# RCMx1_Rev_03.net
KiCad netlist of a schematic drawn in EAGLE
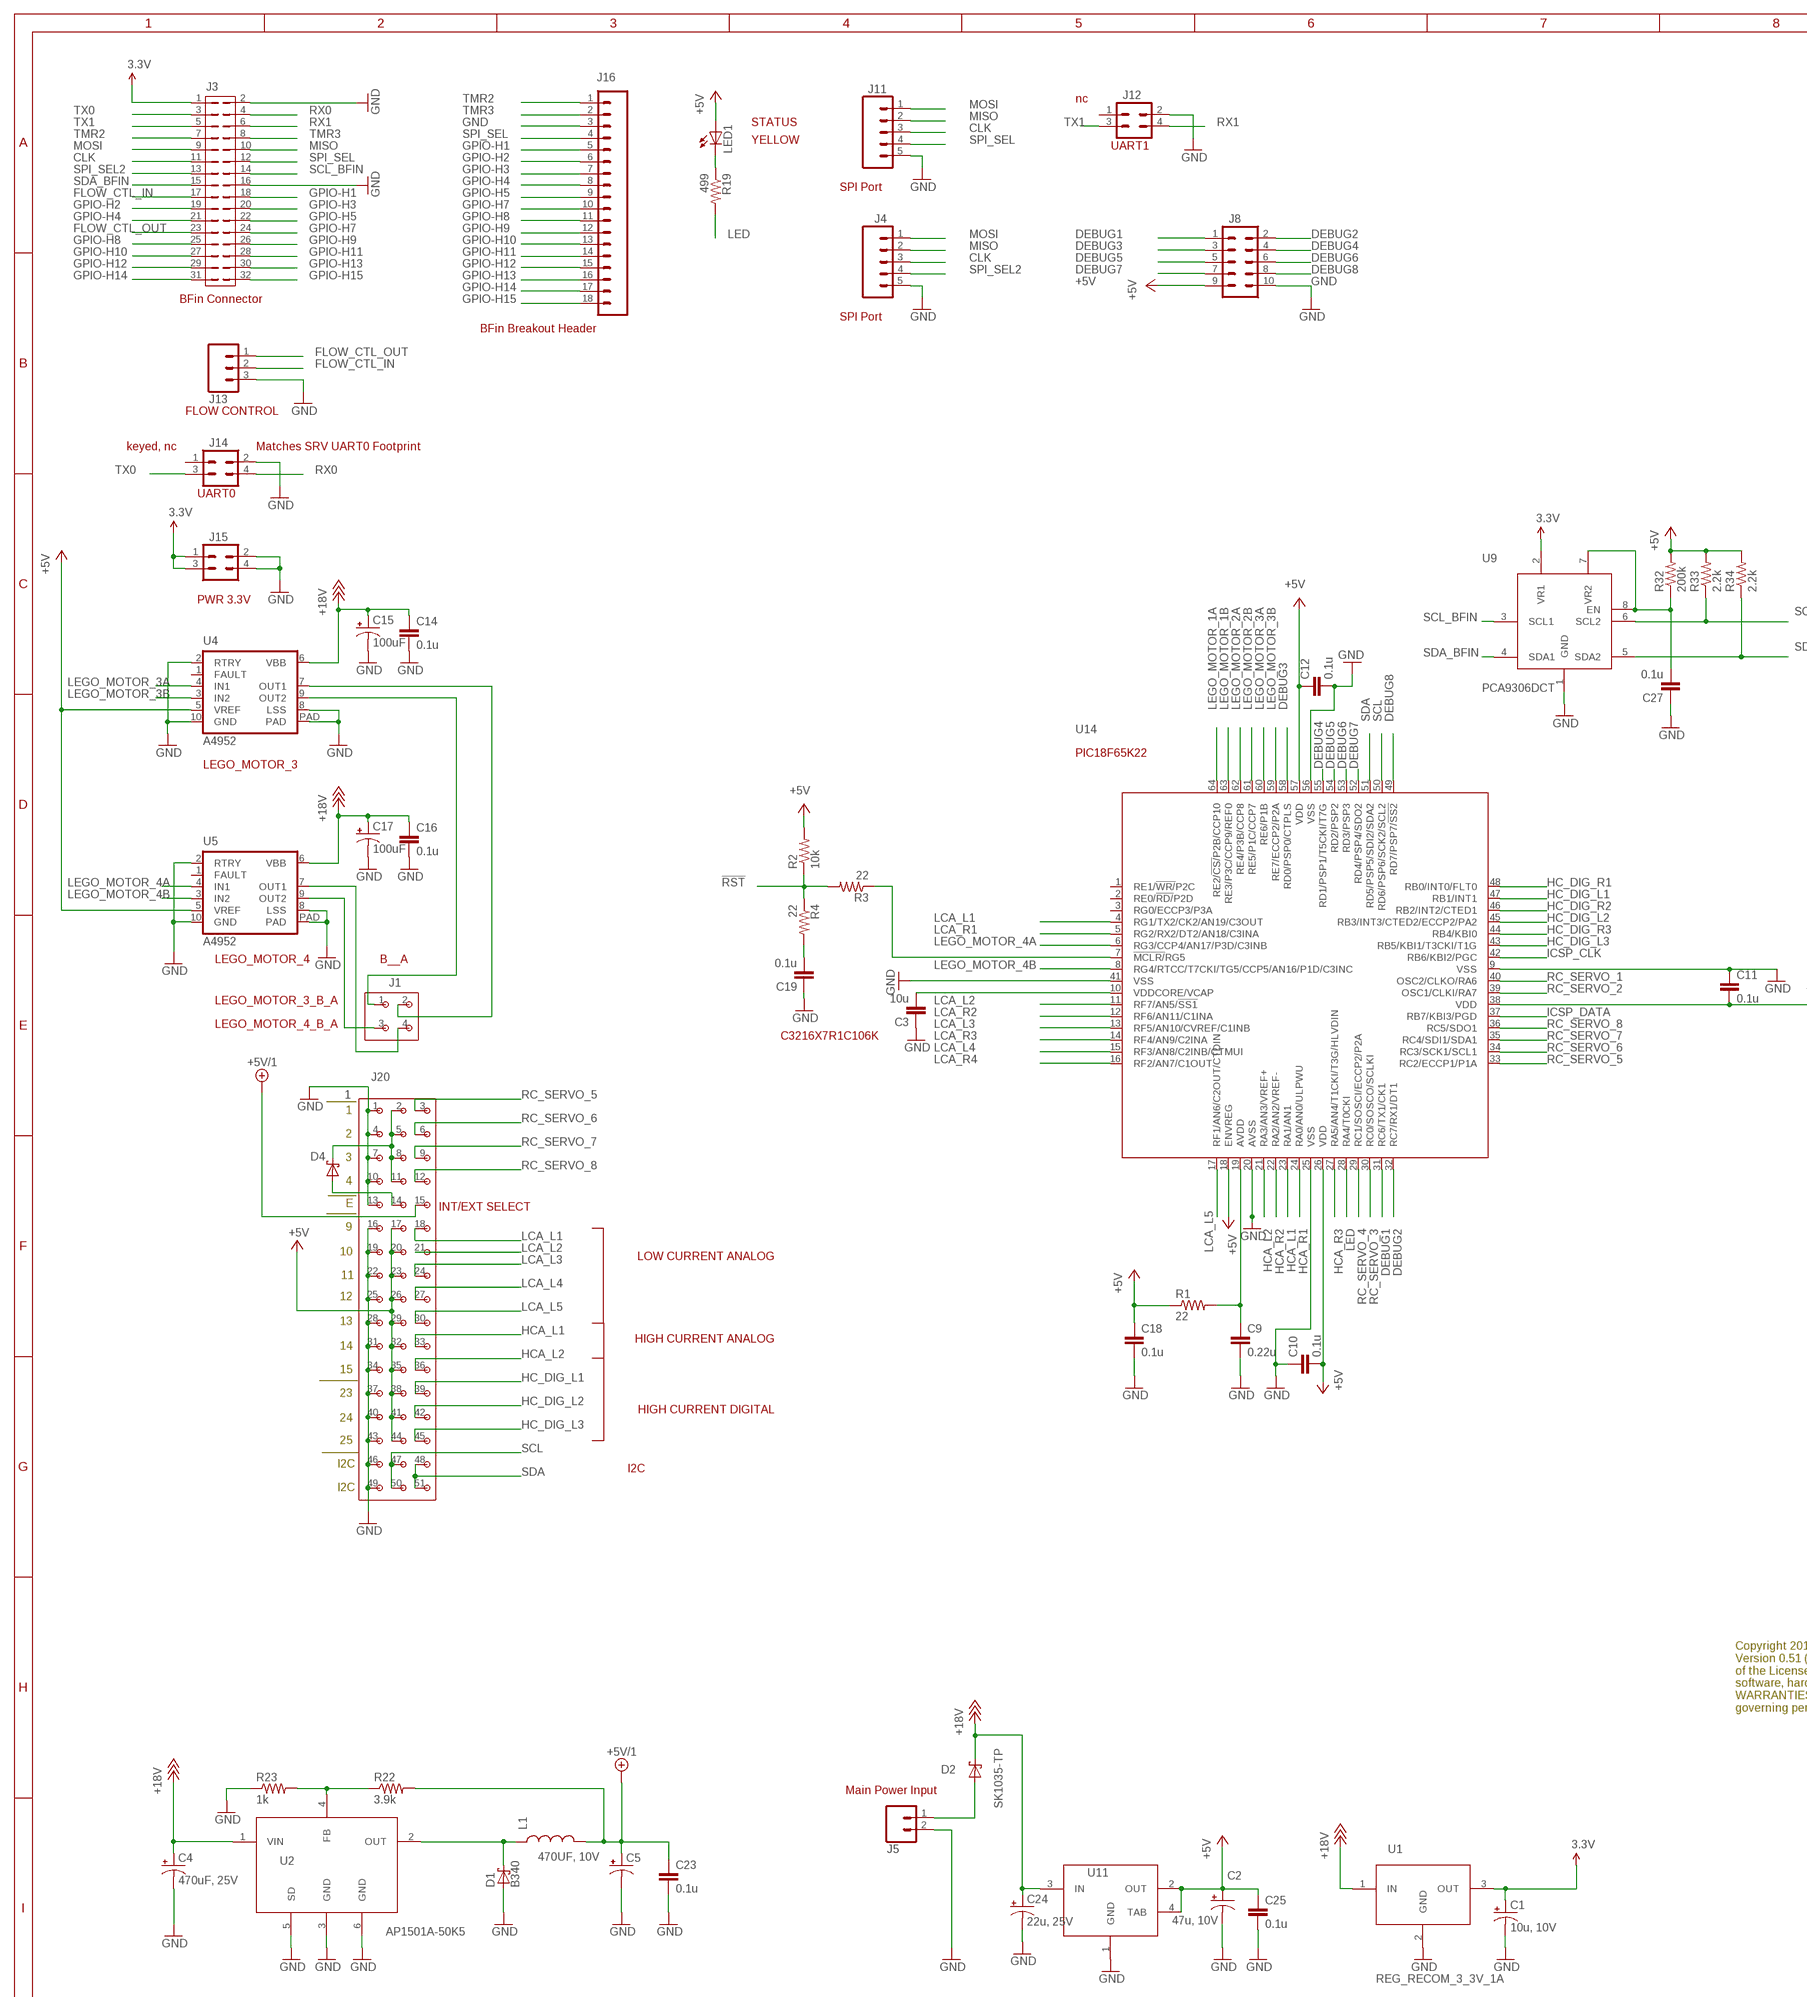
[diagram p0: schematic, sheet 1, part 1 of 2]
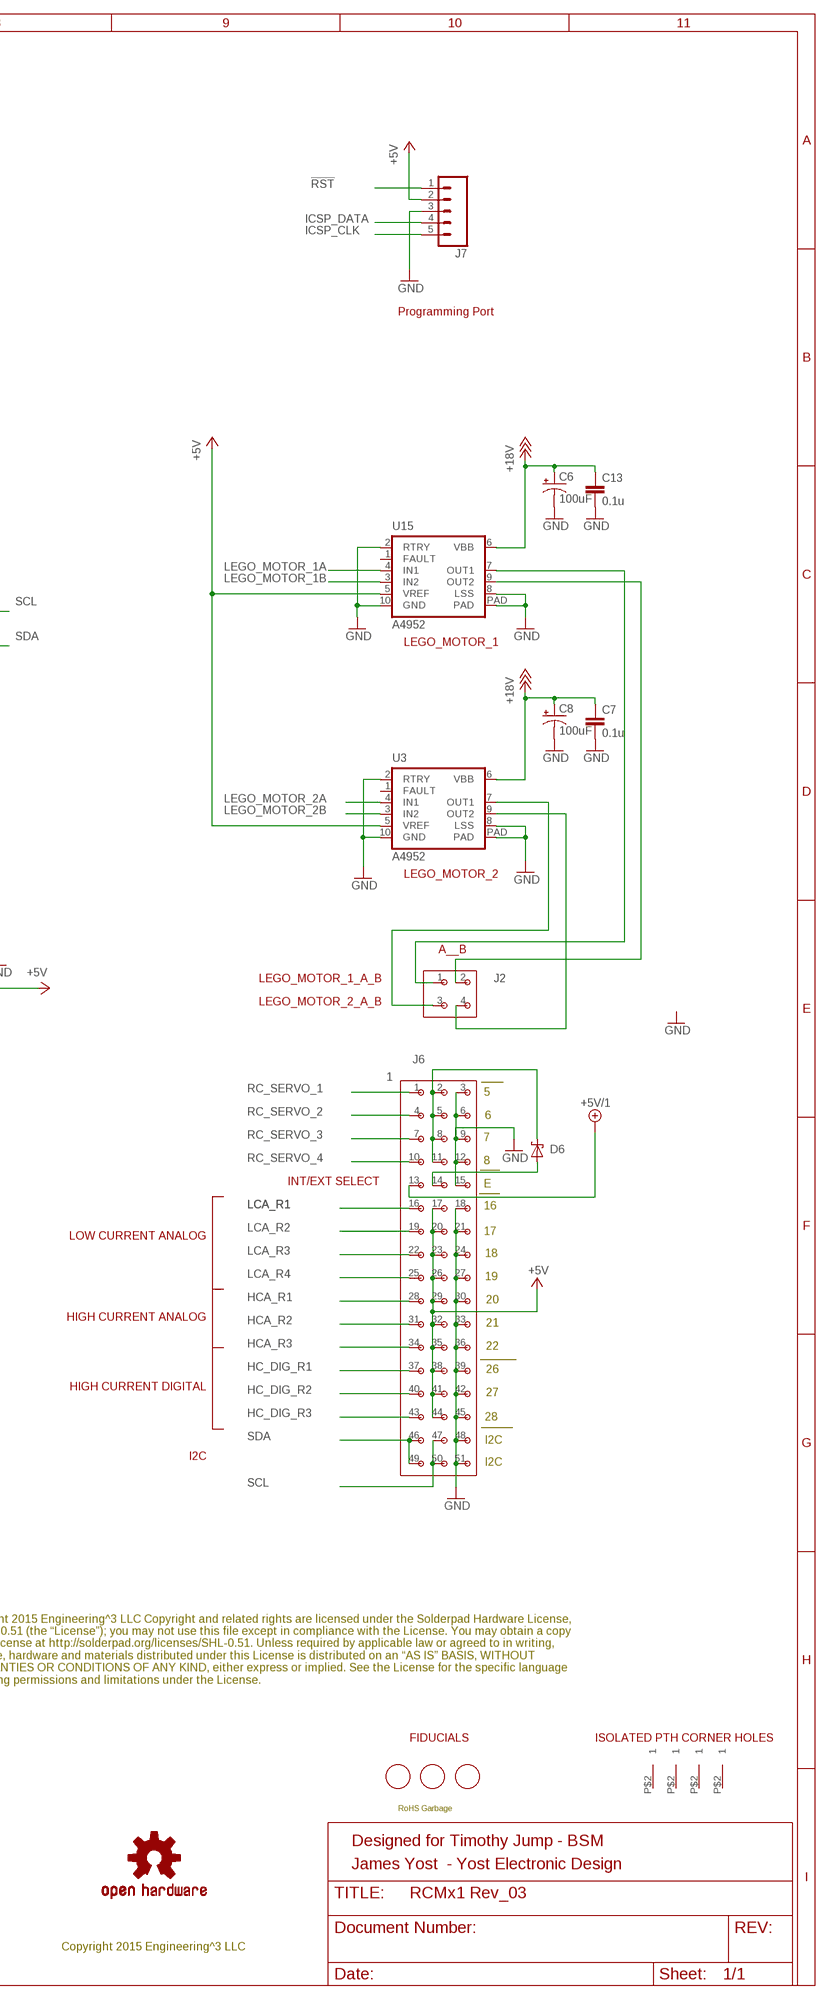
[diagram p1: schematic, sheet 1, part 2 of 2]

(export (version "E")
  (design (tool "Eeschema 10.0.6"))
  (components
    (comp (ref "C1")
      (value "10u, 10V")
      (footprint "eagle-import:EIA3216")
      (libsource (lib "eagle-import") (part "CAP_POL1206"))
    )
    (comp (ref "C2")
      (value "47u, 10V")
      (footprint "eagle-import:CAP1210_POL")
      (libsource (lib "eagle-import") (part "CAP_1210_POL"))
    )
    (comp (ref "C3")
      (value "10u")
      (footprint "eagle-import:1206")
      (libsource (lib "eagle-import") (part "CAP1206"))
    )
    (comp (ref "C4")
      (value "470uF, 25V")
      (footprint "eagle-import:PANASONIC_G")
      (libsource (lib "eagle-import") (part "CAP_POLG"))
    )
    (comp (ref "C5")
      (value "470UF, 10V")
      (footprint "eagle-import:PANASONIC_F")
      (libsource (lib "eagle-import") (part "CAP_ELT_PANASONIC_470UF"))
    )
    (comp (ref "C6")
      (value "100uF")
      (footprint "eagle-import:PANASONIC_D")
      (libsource (lib "eagle-import") (part "CAP_POLD"))
    )
    (comp (ref "C7")
      (value "0.1u")
      (footprint "eagle-import:0805")
      (libsource (lib "eagle-import") (part "CAP0805"))
    )
    (comp (ref "C8")
      (value "100uF")
      (footprint "eagle-import:PANASONIC_D")
      (libsource (lib "eagle-import") (part "CAP_POLD"))
    )
    (comp (ref "C9")
      (value "0.22u")
      (footprint "eagle-import:0805")
      (libsource (lib "eagle-import") (part "CAP0805"))
    )
    (comp (ref "C10")
      (value "0.1u")
      (footprint "eagle-import:0805")
      (libsource (lib "eagle-import") (part "CAP0805"))
    )
    (comp (ref "C11")
      (value "0.1u")
      (footprint "eagle-import:0805")
      (libsource (lib "eagle-import") (part "CAP0805"))
    )
    (comp (ref "C12")
      (value "0.1u")
      (footprint "eagle-import:0805")
      (libsource (lib "eagle-import") (part "CAP0805"))
    )
    (comp (ref "C13")
      (value "0.1u")
      (footprint "eagle-import:0805")
      (libsource (lib "eagle-import") (part "CAP0805"))
    )
    (comp (ref "C14")
      (value "0.1u")
      (footprint "eagle-import:0805")
      (libsource (lib "eagle-import") (part "CAP0805"))
    )
    (comp (ref "C15")
      (value "100uF")
      (footprint "eagle-import:PANASONIC_D")
      (libsource (lib "eagle-import") (part "CAP_POLD"))
    )
    (comp (ref "C16")
      (value "0.1u")
      (footprint "eagle-import:0805")
      (libsource (lib "eagle-import") (part "CAP0805"))
    )
    (comp (ref "C17")
      (value "100uF")
      (footprint "eagle-import:PANASONIC_D")
      (libsource (lib "eagle-import") (part "CAP_POLD"))
    )
    (comp (ref "C18")
      (value "0.1u")
      (footprint "eagle-import:0805")
      (libsource (lib "eagle-import") (part "CAP0805"))
    )
    (comp (ref "C19")
      (value "0.1u")
      (footprint "eagle-import:0805")
      (libsource (lib "eagle-import") (part "CAP0805"))
    )
    (comp (ref "C23")
      (value "0.1u")
      (footprint "eagle-import:0805")
      (libsource (lib "eagle-import") (part "CAP0805"))
    )
    (comp (ref "C24")
      (value "22u, 25V")
      (footprint "eagle-import:CAP1210_POL")
      (libsource (lib "eagle-import") (part "CAP_1210_POL"))
    )
    (comp (ref "C25")
      (value "0.1u")
      (footprint "eagle-import:0805")
      (libsource (lib "eagle-import") (part "CAP0805"))
    )
    (comp (ref "C27")
      (value "0.1u")
      (footprint "eagle-import:0805")
      (libsource (lib "eagle-import") (part "CAP0805"))
    )
    (comp (ref "D1")
      (value "B340")
      (footprint "eagle-import:SMA_DO214AC")
      (libsource (lib "eagle-import") (part "B340"))
    )
    (comp (ref "D2")
      (value "SK1035-TP")
      (footprint "eagle-import:DO214AB")
      (libsource (lib "eagle-import") (part "SK1035-TP"))
    )
    (comp (ref "D4")
      (value "SK1035-TP")
      (footprint "eagle-import:DO214AB")
      (libsource (lib "eagle-import") (part "SK1035-TP"))
    )
    (comp (ref "D6")
      (value "SK1035-TP")
      (footprint "eagle-import:DO214AB")
      (libsource (lib "eagle-import") (part "SK1035-TP"))
    )
    (comp (ref "FID1")
      (value "FIDUCIAL")
      (footprint "eagle-import:FIDUCIAL_1MM")
      (libsource (lib "eagle-import") (part "FIDUCIAL"))
    )
    (comp (ref "FID2")
      (value "FIDUCIAL")
      (footprint "eagle-import:FIDUCIAL_1MM")
      (libsource (lib "eagle-import") (part "FIDUCIAL"))
    )
    (comp (ref "FID3")
      (value "FIDUCIAL")
      (footprint "eagle-import:FIDUCIAL_1MM")
      (libsource (lib "eagle-import") (part "FIDUCIAL"))
    )
    (comp (ref "J1")
      (value "CON_2X2_0_100")
      (footprint "eagle-import:CON_2X2_0_100")
      (libsource (lib "eagle-import") (part "CON_2X2_0_100"))
    )
    (comp (ref "J2")
      (value "CON_2X2_0_100")
      (footprint "eagle-import:CON_2X2_0_100")
      (libsource (lib "eagle-import") (part "CON_2X2_0_100"))
    )
    (comp (ref "J3")
      (value "CON_2X16_0_100")
      (footprint "eagle-import:CON_2X16_0_100")
      (libsource (lib "eagle-import") (part "CON_2X16_0_100"))
    )
    (comp (ref "J4")
      (value "M05PTH")
      (footprint "eagle-import:1X05")
      (libsource (lib "eagle-import") (part "M05PTH"))
    )
    (comp (ref "J5")
      (value "M02NG")
      (footprint "eagle-import:1X02")
      (libsource (lib "eagle-import") (part "M02NG"))
    )
    (comp (ref "J6")
      (value "CON_3X17_0_100")
      (footprint "eagle-import:CON_3X17_0_100")
      (libsource (lib "eagle-import") (part "CON_3X17_0_100"))
    )
    (comp (ref "J7")
      (value "M05PTH")
      (footprint "eagle-import:1X05")
      (libsource (lib "eagle-import") (part "SparkFun-Connectors_M05PTH"))
    )
    (comp (ref "J8")
      (value "M05X2PTH")
      (footprint "eagle-import:AVR_ICSP")
      (libsource (lib "eagle-import") (part "M05X2PTH"))
    )
    (comp (ref "J11")
      (value "M05PTH")
      (footprint "eagle-import:1X05")
      (libsource (lib "eagle-import") (part "M05PTH"))
    )
    (comp (ref "J12")
      (value "CON2X2")
      (footprint "eagle-import:CON2X2")
      (libsource (lib "eagle-import") (part "CON2X2"))
    )
    (comp (ref "J13")
      (value "M03PTH")
      (footprint "eagle-import:1X03")
      (libsource (lib "eagle-import") (part "M03PTH"))
    )
    (comp (ref "J14")
      (value "CON2X2")
      (footprint "eagle-import:CON2X2")
      (libsource (lib "eagle-import") (part "CON2X2"))
    )
    (comp (ref "J15")
      (value "CON2X2")
      (footprint "eagle-import:CON2X2")
      (libsource (lib "eagle-import") (part "CON2X2"))
    )
    (comp (ref "J16")
      (value "CON1X18")
      (footprint "eagle-import:CON1X18")
      (libsource (lib "eagle-import") (part "CON1X18"))
    )
    (comp (ref "J20")
      (value "CON_3X17_0_100")
      (footprint "eagle-import:CON_3X17_0_100")
      (libsource (lib "eagle-import") (part "CON_3X17_0_100"))
    )
    (comp (ref "L1")
      (value "IND_47UH_COILTRONICS_2_95A")
      (footprint "eagle-import:IND_PADS_SMT")
      (libsource (lib "eagle-import") (part "IND_47UH_COILTRONICS_2_95A"))
    )
    (comp (ref "LED1")
      (value "LEDCHIP-LED0805")
      (footprint "eagle-import:CHIP-LED0805")
      (libsource (lib "eagle-import") (part "LEDCHIP-LED0805"))
    )
    (comp (ref "LOGO1")
      (value "OSHW-LOGOM")
      (footprint "eagle-import:OSHW-LOGO-M")
      (libsource (lib "eagle-import") (part "OSHW-LOGOM"))
    )
    (comp (ref "R1")
      (value "22")
      (footprint "eagle-import:0805")
      (libsource (lib "eagle-import") (part "RESISTOR"))
    )
    (comp (ref "R2")
      (value "10k")
      (footprint "eagle-import:0805")
      (libsource (lib "eagle-import") (part "RESISTOR"))
    )
    (comp (ref "R3")
      (value "22")
      (footprint "eagle-import:0805")
      (libsource (lib "eagle-import") (part "RESISTOR"))
    )
    (comp (ref "R4")
      (value "22")
      (footprint "eagle-import:0805")
      (libsource (lib "eagle-import") (part "RESISTOR"))
    )
    (comp (ref "R19")
      (value "499")
      (footprint "eagle-import:0805")
      (libsource (lib "eagle-import") (part "RESISTOR"))
    )
    (comp (ref "R22")
      (value "3.9k")
      (footprint "eagle-import:0805")
      (libsource (lib "eagle-import") (part "RESISTOR"))
    )
    (comp (ref "R23")
      (value "1k")
      (footprint "eagle-import:0805")
      (libsource (lib "eagle-import") (part "RESISTOR"))
    )
    (comp (ref "R32")
      (value "200k")
      (footprint "eagle-import:0805")
      (libsource (lib "eagle-import") (part "RESISTOR"))
    )
    (comp (ref "R33")
      (value "2.2k")
      (footprint "eagle-import:0805")
      (libsource (lib "eagle-import") (part "RESISTOR"))
    )
    (comp (ref "R34")
      (value "2.2k")
      (footprint "eagle-import:0805")
      (libsource (lib "eagle-import") (part "RESISTOR"))
    )
    (comp (ref "U$1")
      (value "GNDPAD")
      (footprint "eagle-import:GNDPAD")
      (libsource (lib "eagle-import") (part "GNDPAD"))
    )
    (comp (ref "U$2")
      (value "GNDPAD")
      (footprint "eagle-import:GNDPAD")
      (libsource (lib "eagle-import") (part "GNDPAD"))
    )
    (comp (ref "U$3")
      (value "ROHS_GARBAGE")
      (footprint "eagle-import:ROHS_GARBAGE_5MM")
      (libsource (lib "eagle-import") (part "ROHS_GARBAGE"))
    )
    (comp (ref "U$7")
      (value "GNDPAD")
      (footprint "eagle-import:GNDPAD")
      (libsource (lib "eagle-import") (part "GNDPAD"))
    )
    (comp (ref "U$8")
      (value "GNDPAD")
      (footprint "eagle-import:GNDPAD")
      (libsource (lib "eagle-import") (part "GNDPAD"))
    )
    (comp (ref "U1")
      (value "REG_RECOM_3_3V_1A")
      (footprint "eagle-import:REG_RECOM_3_3V_1A")
      (libsource (lib "eagle-import") (part "REG_RECOM_3_3V_1A"))
    )
    (comp (ref "U2")
      (value "AP1501A-50K5")
      (footprint "eagle-import:TO263-5")
      (libsource (lib "eagle-import") (part "AP1501A-50K5"))
    )
    (comp (ref "U3")
      (value "A4952")
      (footprint "eagle-import:MSOP10_W_THERMAL_PAD")
      (libsource (lib "eagle-import") (part "A4952"))
    )
    (comp (ref "U4")
      (value "A4952")
      (footprint "eagle-import:MSOP10_W_THERMAL_PAD")
      (libsource (lib "eagle-import") (part "A4952"))
    )
    (comp (ref "U5")
      (value "A4952")
      (footprint "eagle-import:MSOP10_W_THERMAL_PAD")
      (libsource (lib "eagle-import") (part "A4952"))
    )
    (comp (ref "U9")
      (value "PCA9306DCT")
      (footprint "eagle-import:TEST08")
      (libsource (lib "eagle-import") (part "PCA9306DCT"))
    )
    (comp (ref "U11")
      (value "TLV1117-5")
      (footprint "eagle-import:SOT223")
      (libsource (lib "eagle-import") (part "TLV1117-5"))
    )
    (comp (ref "U14")
      (value "MICRO_C_PIC18F65K22")
      (footprint "eagle-import:64PIN_TQFP_10X10X1MM")
      (libsource (lib "eagle-import") (part "MICRO_C_PIC18F65K22"))
    )
    (comp (ref "U15")
      (value "A4952")
      (footprint "eagle-import:MSOP10_W_THERMAL_PAD")
      (libsource (lib "eagle-import") (part "A4952"))
    )
  )
  (nets
    (net (code "1") (name "+5V") (class "Default")
      (node (ref "C10") (pin "2") (pinfunction "2_2") (pintype "passive"))
      (node (ref "C11") (pin "2") (pinfunction "2_2") (pintype "passive"))
      (node (ref "C12") (pin "1") (pinfunction "1_1") (pintype "passive"))
      (node (ref "C18") (pin "1") (pinfunction "1_1") (pintype "passive"))
      (node (ref "C2") (pin "1") (pinfunction "+_1") (pintype "passive"))
      (node (ref "C25") (pin "1") (pinfunction "1_1") (pintype "passive"))
      (node (ref "J20") (pin "17") (pinfunction "17_17") (pintype "passive"))
      (node (ref "J20") (pin "20") (pinfunction "20_20") (pintype "passive"))
      (node (ref "J20") (pin "23") (pinfunction "23_23") (pintype "passive"))
      (node (ref "J20") (pin "26") (pinfunction "26_26") (pintype "passive"))
      (node (ref "J20") (pin "29") (pinfunction "29_29") (pintype "passive"))
      (node (ref "J20") (pin "32") (pinfunction "32_32") (pintype "passive"))
      (node (ref "J20") (pin "35") (pinfunction "35_35") (pintype "passive"))
      (node (ref "J20") (pin "38") (pinfunction "38_38") (pintype "passive"))
      (node (ref "J20") (pin "41") (pinfunction "41_41") (pintype "passive"))
      (node (ref "J20") (pin "44") (pinfunction "44_44") (pintype "passive"))
      (node (ref "J6") (pin "17") (pinfunction "17_17") (pintype "passive"))
      (node (ref "J6") (pin "20") (pinfunction "20_20") (pintype "passive"))
      (node (ref "J6") (pin "23") (pinfunction "23_23") (pintype "passive"))
      (node (ref "J6") (pin "26") (pinfunction "26_26") (pintype "passive"))
      (node (ref "J6") (pin "29") (pinfunction "29_29") (pintype "passive"))
      (node (ref "J6") (pin "32") (pinfunction "32_32") (pintype "passive"))
      (node (ref "J6") (pin "35") (pinfunction "35_35") (pintype "passive"))
      (node (ref "J6") (pin "38") (pinfunction "38_38") (pintype "passive"))
      (node (ref "J6") (pin "41") (pinfunction "41_41") (pintype "passive"))
      (node (ref "J6") (pin "44") (pinfunction "44_44") (pintype "passive"))
      (node (ref "J7") (pin "2") (pinfunction "2_2") (pintype "passive"))
      (node (ref "J8") (pin "9") (pinfunction "9_9") (pintype "passive"))
      (node (ref "LED1") (pin "A") (pinfunction "A_A") (pintype "passive"))
      (node (ref "R1") (pin "1") (pinfunction "1_1") (pintype "passive"))
      (node (ref "R2") (pin "2") (pinfunction "2_2") (pintype "passive"))
      (node (ref "R32") (pin "2") (pinfunction "2_2") (pintype "passive"))
      (node (ref "R33") (pin "2") (pinfunction "2_2") (pintype "passive"))
      (node (ref "R34") (pin "2") (pinfunction "2_2") (pintype "passive"))
      (node (ref "U11") (pin "2") (pinfunction "OUT_2") (pintype "bidirectional"))
      (node (ref "U11") (pin "4") (pinfunction "TAB_4") (pintype "bidirectional"))
      (node (ref "U14") (pin "18") (pinfunction "ENVREG_18") (pintype "input"))
      (node (ref "U14") (pin "26") (pinfunction "VDD_26") (pintype "power_in"))
      (node (ref "U14") (pin "38") (pinfunction "VDD_38") (pintype "power_in"))
      (node (ref "U14") (pin "57") (pinfunction "VDD_57") (pintype "power_in"))
      (node (ref "U15") (pin "5") (pinfunction "VREF_5") (pintype "passive"))
      (node (ref "U3") (pin "5") (pinfunction "VREF_5") (pintype "passive"))
      (node (ref "U4") (pin "5") (pinfunction "VREF_5") (pintype "passive"))
      (node (ref "U5") (pin "5") (pinfunction "VREF_5") (pintype "passive"))
    )
    (net (code "2") (name "+5V{slash}1") (class "Default")
      (node (ref "C23") (pin "1") (pinfunction "1_1") (pintype "passive"))
      (node (ref "C5") (pin "+") (pinfunction "+_+") (pintype "passive"))
      (node (ref "J20") (pin "15") (pinfunction "15_15") (pintype "passive"))
      (node (ref "J6") (pin "13") (pinfunction "13_13") (pintype "passive"))
      (node (ref "L1") (pin "2") (pinfunction "2_2") (pintype "passive"))
      (node (ref "R22") (pin "2") (pinfunction "2_2") (pintype "passive"))
    )
    (net (code "3") (name "+18V") (class "Default")
      (node (ref "C13") (pin "1") (pinfunction "1_1") (pintype "passive"))
      (node (ref "C14") (pin "1") (pinfunction "1_1") (pintype "passive"))
      (node (ref "C15") (pin "+") (pinfunction "+_+") (pintype "passive"))
      (node (ref "C16") (pin "1") (pinfunction "1_1") (pintype "passive"))
      (node (ref "C17") (pin "+") (pinfunction "+_+") (pintype "passive"))
      (node (ref "C24") (pin "1") (pinfunction "+_1") (pintype "passive"))
      (node (ref "C4") (pin "+") (pinfunction "+_+") (pintype "passive"))
      (node (ref "C6") (pin "+") (pinfunction "+_+") (pintype "passive"))
      (node (ref "C7") (pin "1") (pinfunction "1_1") (pintype "passive"))
      (node (ref "C8") (pin "+") (pinfunction "+_+") (pintype "passive"))
      (node (ref "D2") (pin "1") (pinfunction "C_1") (pintype "passive"))
      (node (ref "U1") (pin "1") (pinfunction "IN_1") (pintype "bidirectional"))
      (node (ref "U11") (pin "3") (pinfunction "IN_3") (pintype "bidirectional"))
      (node (ref "U15") (pin "6") (pinfunction "VBB_6") (pintype "input"))
      (node (ref "U2") (pin "1") (pinfunction "VIN_1") (pintype "bidirectional"))
      (node (ref "U3") (pin "6") (pinfunction "VBB_6") (pintype "input"))
      (node (ref "U4") (pin "6") (pinfunction "VBB_6") (pintype "input"))
      (node (ref "U5") (pin "6") (pinfunction "VBB_6") (pintype "input"))
    )
    (net (code "4") (name "/CLK") (class "Default")
      (node (ref "J11") (pin "3") (pinfunction "3_3") (pintype "passive"))
      (node (ref "J3") (pin "11") (pinfunction "11_11") (pintype "passive"))
      (node (ref "J4") (pin "3") (pinfunction "3_3") (pintype "passive"))
    )
    (net (code "5") (name "/DEBUG1") (class "Default")
      (node (ref "J8") (pin "1") (pinfunction "1_1") (pintype "passive"))
      (node (ref "U14") (pin "31") (pinfunction "RC6/TX1/CK1_31") (pintype "bidirectional"))
    )
    (net (code "6") (name "/DEBUG2") (class "Default")
      (node (ref "J8") (pin "2") (pinfunction "2_2") (pintype "passive"))
      (node (ref "U14") (pin "32") (pinfunction "RC7/RX1/DT1_32") (pintype "bidirectional"))
    )
    (net (code "7") (name "/DEBUG3") (class "Default")
      (node (ref "J8") (pin "3") (pinfunction "3_3") (pintype "passive"))
      (node (ref "U14") (pin "58") (pinfunction "RD0/PSP0/CTPLS_58") (pintype "bidirectional"))
    )
    (net (code "8") (name "/DEBUG4") (class "Default")
      (node (ref "J8") (pin "4") (pinfunction "4_4") (pintype "passive"))
      (node (ref "U14") (pin "55") (pinfunction "RD1/PSP1/T5CKI/T7G_55") (pintype "bidirectional"))
    )
    (net (code "9") (name "/DEBUG5") (class "Default")
      (node (ref "J8") (pin "5") (pinfunction "5_5") (pintype "passive"))
      (node (ref "U14") (pin "54") (pinfunction "RD2/PSP2_54") (pintype "bidirectional"))
    )
    (net (code "10") (name "/DEBUG6") (class "Default")
      (node (ref "J8") (pin "6") (pinfunction "6_6") (pintype "passive"))
      (node (ref "U14") (pin "53") (pinfunction "RD3/PSP3_53") (pintype "bidirectional"))
    )
    (net (code "11") (name "/DEBUG7") (class "Default")
      (node (ref "J8") (pin "7") (pinfunction "7_7") (pintype "passive"))
      (node (ref "U14") (pin "52") (pinfunction "RD4/PSP4/SDO2_52") (pintype "bidirectional"))
    )
    (net (code "12") (name "/DEBUG8") (class "Default")
      (node (ref "J8") (pin "8") (pinfunction "8_8") (pintype "passive"))
      (node (ref "U14") (pin "49") (pinfunction "RD7/PSP7/~{SS2}_49") (pintype "bidirectional"))
    )
    (net (code "13") (name "/FLOW_CTL_IN") (class "Default")
      (node (ref "J13") (pin "2") (pinfunction "2_2") (pintype "passive"))
      (node (ref "J3") (pin "17") (pinfunction "17_17") (pintype "passive"))
    )
    (net (code "14") (name "/FLOW_CTL_OUT") (class "Default")
      (node (ref "J13") (pin "1") (pinfunction "1_1") (pintype "passive"))
      (node (ref "J3") (pin "23") (pinfunction "23_23") (pintype "passive"))
    )
    (net (code "15") (name "/GPIO-H1") (class "Default")
      (node (ref "J16") (pin "5") (pinfunction "5_5") (pintype "passive"))
      (node (ref "J3") (pin "18") (pinfunction "18_18") (pintype "passive"))
    )
    (net (code "16") (name "/GPIO-H2") (class "Default")
      (node (ref "J16") (pin "6") (pinfunction "6_6") (pintype "passive"))
      (node (ref "J3") (pin "19") (pinfunction "19_19") (pintype "passive"))
    )
    (net (code "17") (name "/GPIO-H3") (class "Default")
      (node (ref "J16") (pin "7") (pinfunction "7_7") (pintype "passive"))
      (node (ref "J3") (pin "20") (pinfunction "20_20") (pintype "passive"))
    )
    (net (code "18") (name "/GPIO-H4") (class "Default")
      (node (ref "J16") (pin "8") (pinfunction "8_8") (pintype "passive"))
      (node (ref "J3") (pin "21") (pinfunction "21_21") (pintype "passive"))
    )
    (net (code "19") (name "/GPIO-H5") (class "Default")
      (node (ref "J16") (pin "9") (pinfunction "9_9") (pintype "passive"))
      (node (ref "J3") (pin "22") (pinfunction "22_22") (pintype "passive"))
    )
    (net (code "20") (name "/GPIO-H7") (class "Default")
      (node (ref "J16") (pin "10") (pinfunction "10_10") (pintype "passive"))
      (node (ref "J3") (pin "24") (pinfunction "24_24") (pintype "passive"))
    )
    (net (code "21") (name "/GPIO-H8") (class "Default")
      (node (ref "J16") (pin "11") (pinfunction "11_11") (pintype "passive"))
      (node (ref "J3") (pin "25") (pinfunction "25_25") (pintype "passive"))
    )
    (net (code "22") (name "/GPIO-H9") (class "Default")
      (node (ref "J16") (pin "12") (pinfunction "12_12") (pintype "passive"))
      (node (ref "J3") (pin "26") (pinfunction "26_26") (pintype "passive"))
    )
    (net (code "23") (name "/GPIO-H10") (class "Default")
      (node (ref "J16") (pin "13") (pinfunction "13_13") (pintype "passive"))
      (node (ref "J3") (pin "27") (pinfunction "27_27") (pintype "passive"))
    )
    (net (code "24") (name "/GPIO-H11") (class "Default")
      (node (ref "J16") (pin "14") (pinfunction "14_14") (pintype "passive"))
      (node (ref "J3") (pin "28") (pinfunction "28_28") (pintype "passive"))
    )
    (net (code "25") (name "/GPIO-H12") (class "Default")
      (node (ref "J16") (pin "15") (pinfunction "15_15") (pintype "passive"))
      (node (ref "J3") (pin "29") (pinfunction "29_29") (pintype "passive"))
    )
    (net (code "26") (name "/GPIO-H13") (class "Default")
      (node (ref "J16") (pin "16") (pinfunction "16_16") (pintype "passive"))
      (node (ref "J3") (pin "30") (pinfunction "30_30") (pintype "passive"))
    )
    (net (code "27") (name "/GPIO-H14") (class "Default")
      (node (ref "J16") (pin "17") (pinfunction "17_17") (pintype "passive"))
      (node (ref "J3") (pin "31") (pinfunction "31_31") (pintype "passive"))
    )
    (net (code "28") (name "/GPIO-H15") (class "Default")
      (node (ref "J16") (pin "18") (pinfunction "18_18") (pintype "passive"))
      (node (ref "J3") (pin "32") (pinfunction "32_32") (pintype "passive"))
    )
    (net (code "29") (name "/HCA_L1") (class "Default")
      (node (ref "J20") (pin "33") (pinfunction "33_33") (pintype "passive"))
      (node (ref "U14") (pin "23") (pinfunction "RA1/AN1_23") (pintype "bidirectional"))
    )
    (net (code "30") (name "/HCA_L2") (class "Default")
      (node (ref "J20") (pin "36") (pinfunction "36_36") (pintype "passive"))
      (node (ref "U14") (pin "21") (pinfunction "RA3/AN3/VREF+_21") (pintype "bidirectional"))
    )
    (net (code "31") (name "/HCA_R1") (class "Default")
      (node (ref "J6") (pin "28") (pinfunction "28_28") (pintype "passive"))
      (node (ref "U14") (pin "24") (pinfunction "RA0/AN0/ULPWU_24") (pintype "bidirectional"))
    )
    (net (code "32") (name "/HCA_R2") (class "Default")
      (node (ref "J6") (pin "31") (pinfunction "31_31") (pintype "passive"))
      (node (ref "U14") (pin "22") (pinfunction "RA2/AN2/VREF-_22") (pintype "bidirectional"))
    )
    (net (code "33") (name "/HCA_R3") (class "Default")
      (node (ref "J6") (pin "34") (pinfunction "34_34") (pintype "passive"))
      (node (ref "U14") (pin "27") (pinfunction "RA5/AN4/T1CKI/T3G/HLVDIN_27") (pintype "bidirectional"))
    )
    (net (code "34") (name "/HC_DIG_L1") (class "Default")
      (node (ref "J20") (pin "39") (pinfunction "39_39") (pintype "passive"))
      (node (ref "U14") (pin "47") (pinfunction "RB1/INT1_47") (pintype "bidirectional"))
    )
    (net (code "35") (name "/HC_DIG_L2") (class "Default")
      (node (ref "J20") (pin "42") (pinfunction "42_42") (pintype "passive"))
      (node (ref "U14") (pin "45") (pinfunction "RB3/INT3/CTED2/ECCP2/PA2_45") (pintype "bidirectional"))
    )
    (net (code "36") (name "/HC_DIG_L3") (class "Default")
      (node (ref "J20") (pin "45") (pinfunction "45_45") (pintype "passive"))
      (node (ref "U14") (pin "43") (pinfunction "RB5/KBI1/T3CKI/T1G_43") (pintype "bidirectional"))
    )
    (net (code "37") (name "/HC_DIG_R1") (class "Default")
      (node (ref "J6") (pin "37") (pinfunction "37_37") (pintype "passive"))
      (node (ref "U14") (pin "48") (pinfunction "RB0/INT0/FLT0_48") (pintype "bidirectional"))
    )
    (net (code "38") (name "/HC_DIG_R2") (class "Default")
      (node (ref "J6") (pin "40") (pinfunction "40_40") (pintype "passive"))
      (node (ref "U14") (pin "46") (pinfunction "RB2/INT2/CTED1_46") (pintype "bidirectional"))
    )
    (net (code "39") (name "/HC_DIG_R3") (class "Default")
      (node (ref "J6") (pin "43") (pinfunction "43_43") (pintype "passive"))
      (node (ref "U14") (pin "44") (pinfunction "RB4/KBI0_44") (pintype "bidirectional"))
    )
    (net (code "40") (name "/ICSP_CLK") (class "Default")
      (node (ref "J7") (pin "5") (pinfunction "5_5") (pintype "passive"))
      (node (ref "U14") (pin "42") (pinfunction "RB6/KBI2/PGC_42") (pintype "bidirectional"))
    )
    (net (code "41") (name "/ICSP_DATA") (class "Default")
      (node (ref "J7") (pin "4") (pinfunction "4_4") (pintype "passive"))
      (node (ref "U14") (pin "37") (pinfunction "RB7/KBI3/PGD_37") (pintype "bidirectional"))
    )
    (net (code "42") (name "/LCA_L1") (class "Default")
      (node (ref "J20") (pin "18") (pinfunction "18_18") (pintype "passive"))
      (node (ref "U14") (pin "4") (pinfunction "RG1/TX2/CK2/AN19/C3OUT_4") (pintype "bidirectional"))
    )
    (net (code "43") (name "/LCA_L2") (class "Default")
      (node (ref "J20") (pin "21") (pinfunction "21_21") (pintype "passive"))
      (node (ref "U14") (pin "11") (pinfunction "RF7/AN5/~{SS1}_11") (pintype "bidirectional"))
    )
    (net (code "44") (name "/LCA_L3") (class "Default")
      (node (ref "J20") (pin "24") (pinfunction "24_24") (pintype "passive"))
      (node (ref "U14") (pin "13") (pinfunction "RF5/AN10/CVREF/C1INB_13") (pintype "bidirectional"))
    )
    (net (code "45") (name "/LCA_L4") (class "Default")
      (node (ref "J20") (pin "27") (pinfunction "27_27") (pintype "passive"))
      (node (ref "U14") (pin "15") (pinfunction "RF3/AN8/C2INB/CTMUI_15") (pintype "bidirectional"))
    )
    (net (code "46") (name "/LCA_L5") (class "Default")
      (node (ref "J20") (pin "30") (pinfunction "30_30") (pintype "passive"))
      (node (ref "U14") (pin "17") (pinfunction "RF1/AN6/C2OUT/CTDIN_17") (pintype "bidirectional"))
    )
    (net (code "47") (name "/LCA_R1") (class "Default")
      (node (ref "J6") (pin "16") (pinfunction "16_16") (pintype "passive"))
      (node (ref "U14") (pin "5") (pinfunction "RG2/RX2/DT2/AN18/C3INA_5") (pintype "bidirectional"))
    )
    (net (code "48") (name "/LCA_R2") (class "Default")
      (node (ref "J6") (pin "19") (pinfunction "19_19") (pintype "passive"))
      (node (ref "U14") (pin "12") (pinfunction "RF6/AN11/C1INA_12") (pintype "bidirectional"))
    )
    (net (code "49") (name "/LCA_R3") (class "Default")
      (node (ref "J6") (pin "22") (pinfunction "22_22") (pintype "passive"))
      (node (ref "U14") (pin "14") (pinfunction "RF4/AN9/C2INA_14") (pintype "bidirectional"))
    )
    (net (code "50") (name "/LCA_R4") (class "Default")
      (node (ref "J6") (pin "25") (pinfunction "25_25") (pintype "passive"))
      (node (ref "U14") (pin "16") (pinfunction "RF2/AN7/C1OUT_16") (pintype "bidirectional"))
    )
    (net (code "51") (name "/LED") (class "Default")
      (node (ref "R19") (pin "2") (pinfunction "2_2") (pintype "passive"))
      (node (ref "U14") (pin "28") (pinfunction "RA4/T0CKI_28") (pintype "bidirectional"))
    )
    (net (code "52") (name "/LEGO_MOTOR_1A") (class "Default")
      (node (ref "U14") (pin "64") (pinfunction "RE2/~{CS/}P2B/CCP10_64") (pintype "bidirectional"))
      (node (ref "U15") (pin "4") (pinfunction "IN1_4") (pintype "input"))
    )
    (net (code "53") (name "/LEGO_MOTOR_1B") (class "Default")
      (node (ref "U14") (pin "63") (pinfunction "RE3/P3C/CCP9/REF0_63") (pintype "bidirectional"))
      (node (ref "U15") (pin "3") (pinfunction "IN2_3") (pintype "input"))
    )
    (net (code "54") (name "/LEGO_MOTOR_2A") (class "Default")
      (node (ref "U14") (pin "62") (pinfunction "RE4/P3B/CCP8_62") (pintype "bidirectional"))
      (node (ref "U3") (pin "4") (pinfunction "IN1_4") (pintype "input"))
    )
    (net (code "55") (name "/LEGO_MOTOR_2B") (class "Default")
      (node (ref "U14") (pin "61") (pinfunction "RE5/P1C/CCP7_61") (pintype "bidirectional"))
      (node (ref "U3") (pin "3") (pinfunction "IN2_3") (pintype "input"))
    )
    (net (code "56") (name "/LEGO_MOTOR_3A") (class "Default")
      (node (ref "U14") (pin "60") (pinfunction "RE6/P1B_60") (pintype "bidirectional"))
      (node (ref "U4") (pin "4") (pinfunction "IN1_4") (pintype "input"))
    )
    (net (code "57") (name "/LEGO_MOTOR_3B") (class "Default")
      (node (ref "U14") (pin "59") (pinfunction "RE7/ECCP2/P2A_59") (pintype "bidirectional"))
      (node (ref "U4") (pin "3") (pinfunction "IN2_3") (pintype "input"))
    )
    (net (code "58") (name "/LEGO_MOTOR_4A") (class "Default")
      (node (ref "U14") (pin "6") (pinfunction "RG3/CCP4/AN17/P3D/C3INB_6") (pintype "bidirectional"))
      (node (ref "U5") (pin "4") (pinfunction "IN1_4") (pintype "input"))
    )
    (net (code "59") (name "/LEGO_MOTOR_4B") (class "Default")
      (node (ref "U14") (pin "8") (pinfunction "RG4/RTCC/T7CKI/TG5/CCP5/AN16/P1D/C3INC_8") (pintype "bidirectional"))
      (node (ref "U5") (pin "3") (pinfunction "IN2_3") (pintype "input"))
    )
    (net (code "60") (name "/MISO") (class "Default")
      (node (ref "J11") (pin "2") (pinfunction "2_2") (pintype "passive"))
      (node (ref "J3") (pin "10") (pinfunction "10_10") (pintype "passive"))
      (node (ref "J4") (pin "2") (pinfunction "2_2") (pintype "passive"))
    )
    (net (code "61") (name "/MOSI") (class "Default")
      (node (ref "J11") (pin "1") (pinfunction "1_1") (pintype "passive"))
      (node (ref "J3") (pin "9") (pinfunction "9_9") (pintype "passive"))
      (node (ref "J4") (pin "1") (pinfunction "1_1") (pintype "passive"))
    )
    (net (code "62") (name "/RC_SERVO_1") (class "Default")
      (node (ref "J6") (pin "1") (pinfunction "1_1") (pintype "passive"))
      (node (ref "U14") (pin "40") (pinfunction "OSC2/CLKO/RA6_40") (pintype "output"))
    )
    (net (code "63") (name "/RC_SERVO_2") (class "Default")
      (node (ref "J6") (pin "4") (pinfunction "4_4") (pintype "passive"))
      (node (ref "U14") (pin "39") (pinfunction "OSC1/CLKI/RA7_39") (pintype "input"))
    )
    (net (code "64") (name "/RC_SERVO_3") (class "Default")
      (node (ref "J6") (pin "7") (pinfunction "7_7") (pintype "passive"))
      (node (ref "U14") (pin "30") (pinfunction "RC0/SOSCO/SCLKI_30") (pintype "bidirectional"))
    )
    (net (code "65") (name "/RC_SERVO_4") (class "Default")
      (node (ref "J6") (pin "10") (pinfunction "10_10") (pintype "passive"))
      (node (ref "U14") (pin "29") (pinfunction "RC1/SOSCI/ECCP2/P2A_29") (pintype "bidirectional"))
    )
    (net (code "66") (name "/RC_SERVO_5") (class "Default")
      (node (ref "J20") (pin "3") (pinfunction "3_3") (pintype "passive"))
      (node (ref "U14") (pin "33") (pinfunction "RC2/ECCP1/P1A_33") (pintype "bidirectional"))
    )
    (net (code "67") (name "/RC_SERVO_6") (class "Default")
      (node (ref "J20") (pin "6") (pinfunction "6_6") (pintype "passive"))
      (node (ref "U14") (pin "34") (pinfunction "RC3/SCK1/SCL1_34") (pintype "bidirectional"))
    )
    (net (code "68") (name "/RC_SERVO_7") (class "Default")
      (node (ref "J20") (pin "9") (pinfunction "9_9") (pintype "passive"))
      (node (ref "U14") (pin "35") (pinfunction "RC4/SDI1/SDA1_35") (pintype "bidirectional"))
    )
    (net (code "69") (name "/RC_SERVO_8") (class "Default")
      (node (ref "J20") (pin "12") (pinfunction "12_12") (pintype "passive"))
      (node (ref "U14") (pin "36") (pinfunction "RC5/SDO1_36") (pintype "bidirectional"))
    )
    (net (code "70") (name "/RX0") (class "Default")
      (node (ref "J14") (pin "4") (pinfunction "4_4") (pintype "passive"))
      (node (ref "J3") (pin "4") (pinfunction "4_4") (pintype "passive"))
    )
    (net (code "71") (name "/RX1") (class "Default")
      (node (ref "J12") (pin "4") (pinfunction "4_4") (pintype "passive"))
      (node (ref "J3") (pin "6") (pinfunction "6_6") (pintype "passive"))
    )
    (net (code "72") (name "/SCL") (class "Default")
      (node (ref "J20") (pin "47") (pinfunction "47_47") (pintype "passive"))
      (node (ref "J20") (pin "50") (pinfunction "50_50") (pintype "passive"))
      (node (ref "J6") (pin "47") (pinfunction "47_47") (pintype "passive"))
      (node (ref "J6") (pin "50") (pinfunction "50_50") (pintype "passive"))
      (node (ref "R33") (pin "1") (pinfunction "1_1") (pintype "passive"))
      (node (ref "U14") (pin "50") (pinfunction "RD6/PSP6/SCK2/SCL2_50") (pintype "bidirectional"))
      (node (ref "U9") (pin "6") (pinfunction "SCL2_6") (pintype "bidirectional"))
    )
    (net (code "73") (name "/SCL_BFIN") (class "Default")
      (node (ref "J3") (pin "14") (pinfunction "14_14") (pintype "passive"))
      (node (ref "U9") (pin "3") (pinfunction "SCL1_3") (pintype "bidirectional"))
    )
    (net (code "74") (name "/SDA") (class "Default")
      (node (ref "J20") (pin "48") (pinfunction "48_48") (pintype "passive"))
      (node (ref "J20") (pin "51") (pinfunction "51_51") (pintype "passive"))
      (node (ref "J6") (pin "46") (pinfunction "46_46") (pintype "passive"))
      (node (ref "J6") (pin "49") (pinfunction "49_49") (pintype "passive"))
      (node (ref "R34") (pin "1") (pinfunction "1_1") (pintype "passive"))
      (node (ref "U14") (pin "51") (pinfunction "RD5/PSP5/SDI2/SDA2_51") (pintype "bidirectional"))
      (node (ref "U9") (pin "5") (pinfunction "SDA2_5") (pintype "bidirectional"))
    )
    (net (code "75") (name "/SDA_BFIN") (class "Default")
      (node (ref "J3") (pin "15") (pinfunction "15_15") (pintype "passive"))
      (node (ref "U9") (pin "4") (pinfunction "SDA1_4") (pintype "bidirectional"))
    )
    (net (code "76") (name "/SPI_SEL") (class "Default")
      (node (ref "J11") (pin "4") (pinfunction "4_4") (pintype "passive"))
      (node (ref "J16") (pin "4") (pinfunction "4_4") (pintype "passive"))
      (node (ref "J3") (pin "12") (pinfunction "12_12") (pintype "passive"))
    )
    (net (code "77") (name "/SPI_SEL2") (class "Default")
      (node (ref "J3") (pin "13") (pinfunction "13_13") (pintype "passive"))
      (node (ref "J4") (pin "4") (pinfunction "4_4") (pintype "passive"))
    )
    (net (code "78") (name "/TMR2") (class "Default")
      (node (ref "J16") (pin "1") (pinfunction "1_1") (pintype "passive"))
      (node (ref "J3") (pin "7") (pinfunction "7_7") (pintype "passive"))
    )
    (net (code "79") (name "/TMR3") (class "Default")
      (node (ref "J16") (pin "2") (pinfunction "2_2") (pintype "passive"))
      (node (ref "J3") (pin "8") (pinfunction "8_8") (pintype "passive"))
    )
    (net (code "80") (name "/TX0") (class "Default")
      (node (ref "J14") (pin "3") (pinfunction "3_3") (pintype "passive"))
      (node (ref "J3") (pin "3") (pinfunction "3_3") (pintype "passive"))
    )
    (net (code "81") (name "/TX1") (class "Default")
      (node (ref "J12") (pin "3") (pinfunction "3_3") (pintype "passive"))
      (node (ref "J3") (pin "5") (pinfunction "5_5") (pintype "passive"))
    )
    (net (code "82") (name "/~{RST}") (class "Default")
      (node (ref "J7") (pin "1") (pinfunction "1_1") (pintype "passive"))
      (node (ref "R2") (pin "1") (pinfunction "1_1") (pintype "passive"))
      (node (ref "R3") (pin "2") (pinfunction "2_2") (pintype "passive"))
      (node (ref "R4") (pin "1") (pinfunction "1_1") (pintype "passive"))
    )
    (net (code "83") (name "3.3V") (class "Default")
      (node (ref "C1") (pin "A") (pinfunction "+_A") (pintype "passive"))
      (node (ref "J15") (pin "1") (pinfunction "1_1") (pintype "passive"))
      (node (ref "J15") (pin "3") (pinfunction "3_3") (pintype "passive"))
      (node (ref "J3") (pin "1") (pinfunction "1_1") (pintype "passive"))
      (node (ref "U1") (pin "3") (pinfunction "OUT_3") (pintype "bidirectional"))
      (node (ref "U9") (pin "2") (pinfunction "VR1_2") (pintype "bidirectional"))
    )
    (net (code "84") (name "GND") (class "Default")
      (node (ref "C1") (pin "C") (pinfunction "-_C") (pintype "passive"))
      (node (ref "C10") (pin "1") (pinfunction "1_1") (pintype "passive"))
      (node (ref "C11") (pin "1") (pinfunction "1_1") (pintype "passive"))
      (node (ref "C12") (pin "2") (pinfunction "2_2") (pintype "passive"))
      (node (ref "C13") (pin "2") (pinfunction "2_2") (pintype "passive"))
      (node (ref "C14") (pin "2") (pinfunction "2_2") (pintype "passive"))
      (node (ref "C15") (pin "-") (pinfunction "-_-") (pintype "passive"))
      (node (ref "C16") (pin "2") (pinfunction "2_2") (pintype "passive"))
      (node (ref "C17") (pin "-") (pinfunction "-_-") (pintype "passive"))
      (node (ref "C18") (pin "2") (pinfunction "2_2") (pintype "passive"))
      (node (ref "C19") (pin "1") (pinfunction "1_1") (pintype "passive"))
      (node (ref "C2") (pin "2") (pinfunction "-_2") (pintype "passive"))
      (node (ref "C23") (pin "2") (pinfunction "2_2") (pintype "passive"))
      (node (ref "C24") (pin "2") (pinfunction "-_2") (pintype "passive"))
      (node (ref "C25") (pin "2") (pinfunction "2_2") (pintype "passive"))
      (node (ref "C27") (pin "1") (pinfunction "1_1") (pintype "passive"))
      (node (ref "C3") (pin "1") (pinfunction "1_1") (pintype "passive"))
      (node (ref "C4") (pin "-") (pinfunction "-_-") (pintype "passive"))
      (node (ref "C5") (pin "-") (pinfunction "-_-") (pintype "passive"))
      (node (ref "C6") (pin "-") (pinfunction "-_-") (pintype "passive"))
      (node (ref "C7") (pin "2") (pinfunction "2_2") (pintype "passive"))
      (node (ref "C8") (pin "-") (pinfunction "-_-") (pintype "passive"))
      (node (ref "C9") (pin "2") (pinfunction "2_2") (pintype "passive"))
      (node (ref "D1") (pin "A") (pinfunction "A_A") (pintype "passive"))
      (node (ref "J11") (pin "5") (pinfunction "5_5") (pintype "passive"))
      (node (ref "J12") (pin "2") (pinfunction "2_2") (pintype "passive"))
      (node (ref "J13") (pin "3") (pinfunction "3_3") (pintype "passive"))
      (node (ref "J14") (pin "2") (pinfunction "2_2") (pintype "passive"))
      (node (ref "J15") (pin "2") (pinfunction "2_2") (pintype "passive"))
      (node (ref "J15") (pin "4") (pinfunction "4_4") (pintype "passive"))
      (node (ref "J16") (pin "3") (pinfunction "3_3") (pintype "passive"))
      (node (ref "J20") (pin "1") (pinfunction "1_1") (pintype "passive"))
      (node (ref "J20") (pin "10") (pinfunction "10_10") (pintype "passive"))
      (node (ref "J20") (pin "13") (pinfunction "13_13") (pintype "passive"))
      (node (ref "J20") (pin "16") (pinfunction "16_16") (pintype "passive"))
      (node (ref "J20") (pin "19") (pinfunction "19_19") (pintype "passive"))
      (node (ref "J20") (pin "22") (pinfunction "22_22") (pintype "passive"))
      (node (ref "J20") (pin "25") (pinfunction "25_25") (pintype "passive"))
      (node (ref "J20") (pin "28") (pinfunction "28_28") (pintype "passive"))
      (node (ref "J20") (pin "31") (pinfunction "31_31") (pintype "passive"))
      (node (ref "J20") (pin "34") (pinfunction "34_34") (pintype "passive"))
      (node (ref "J20") (pin "37") (pinfunction "37_37") (pintype "passive"))
      (node (ref "J20") (pin "4") (pinfunction "4_4") (pintype "passive"))
      (node (ref "J20") (pin "40") (pinfunction "40_40") (pintype "passive"))
      (node (ref "J20") (pin "43") (pinfunction "43_43") (pintype "passive"))
      (node (ref "J20") (pin "46") (pinfunction "46_46") (pintype "passive"))
      (node (ref "J20") (pin "49") (pinfunction "49_49") (pintype "passive"))
      (node (ref "J20") (pin "7") (pinfunction "7_7") (pintype "passive"))
      (node (ref "J3") (pin "16") (pinfunction "16_16") (pintype "passive"))
      (node (ref "J3") (pin "2") (pinfunction "2_2") (pintype "passive"))
      (node (ref "J4") (pin "5") (pinfunction "5_5") (pintype "passive"))
      (node (ref "J5") (pin "2") (pinfunction "2_2") (pintype "passive"))
      (node (ref "J6") (pin "12") (pinfunction "12_12") (pintype "passive"))
      (node (ref "J6") (pin "15") (pinfunction "15_15") (pintype "passive"))
      (node (ref "J6") (pin "18") (pinfunction "18_18") (pintype "passive"))
      (node (ref "J6") (pin "21") (pinfunction "21_21") (pintype "passive"))
      (node (ref "J6") (pin "24") (pinfunction "24_24") (pintype "passive"))
      (node (ref "J6") (pin "27") (pinfunction "27_27") (pintype "passive"))
      (node (ref "J6") (pin "3") (pinfunction "3_3") (pintype "passive"))
      (node (ref "J6") (pin "30") (pinfunction "30_30") (pintype "passive"))
      (node (ref "J6") (pin "33") (pinfunction "33_33") (pintype "passive"))
      (node (ref "J6") (pin "36") (pinfunction "36_36") (pintype "passive"))
      (node (ref "J6") (pin "39") (pinfunction "39_39") (pintype "passive"))
      (node (ref "J6") (pin "42") (pinfunction "42_42") (pintype "passive"))
      (node (ref "J6") (pin "45") (pinfunction "45_45") (pintype "passive"))
      (node (ref "J6") (pin "48") (pinfunction "48_48") (pintype "passive"))
      (node (ref "J6") (pin "51") (pinfunction "51_51") (pintype "passive"))
      (node (ref "J6") (pin "6") (pinfunction "6_6") (pintype "passive"))
      (node (ref "J6") (pin "9") (pinfunction "9_9") (pintype "passive"))
      (node (ref "J7") (pin "3") (pinfunction "3_3") (pintype "passive"))
      (node (ref "J8") (pin "10") (pinfunction "10_10") (pintype "passive"))
      (node (ref "R23") (pin "1") (pinfunction "1_1") (pintype "passive"))
      (node (ref "U1") (pin "2") (pinfunction "GND_2") (pintype "bidirectional"))
      (node (ref "U11") (pin "1") (pinfunction "GND_1") (pintype "bidirectional"))
      (node (ref "U14") (pin "20") (pinfunction "AVSS_20") (pintype "power_in"))
      (node (ref "U14") (pin "25") (pinfunction "VSS_25") (pintype "power_in"))
      (node (ref "U14") (pin "41") (pinfunction "VSS_41") (pintype "power_in"))
      (node (ref "U14") (pin "56") (pinfunction "VSS_56") (pintype "power_in"))
      (node (ref "U14") (pin "9") (pinfunction "VSS_9") (pintype "power_in"))
      (node (ref "U15") (pin "10") (pinfunction "GND_10") (pintype "power_in"))
      (node (ref "U15") (pin "2") (pinfunction "RTRY_2") (pintype "input"))
      (node (ref "U15") (pin "8") (pinfunction "LSS_8") (pintype "output"))
      (node (ref "U15") (pin "PAD") (pinfunction "PAD_PAD") (pintype "output"))
      (node (ref "U2") (pin "3") (pinfunction "GND_3") (pintype "bidirectional"))
      (node (ref "U2") (pin "5") (pinfunction "SD_5") (pintype "bidirectional"))
      (node (ref "U2") (pin "6") (pinfunction "GND_6") (pintype "bidirectional"))
      (node (ref "U3") (pin "10") (pinfunction "GND_10") (pintype "power_in"))
      (node (ref "U3") (pin "2") (pinfunction "RTRY_2") (pintype "input"))
      (node (ref "U3") (pin "8") (pinfunction "LSS_8") (pintype "output"))
      (node (ref "U3") (pin "PAD") (pinfunction "PAD_PAD") (pintype "output"))
      (node (ref "U4") (pin "10") (pinfunction "GND_10") (pintype "power_in"))
      (node (ref "U4") (pin "2") (pinfunction "RTRY_2") (pintype "input"))
      (node (ref "U4") (pin "8") (pinfunction "LSS_8") (pintype "output"))
      (node (ref "U4") (pin "PAD") (pinfunction "PAD_PAD") (pintype "output"))
      (node (ref "U5") (pin "10") (pinfunction "GND_10") (pintype "power_in"))
      (node (ref "U5") (pin "2") (pinfunction "RTRY_2") (pintype "input"))
      (node (ref "U5") (pin "8") (pinfunction "LSS_8") (pintype "output"))
      (node (ref "U5") (pin "PAD") (pinfunction "PAD_PAD") (pintype "output"))
      (node (ref "U9") (pin "1") (pinfunction "GND_1") (pintype "bidirectional"))
    )
    (net (code "85") (name "Net-(C19-Pad2)") (class "Default")
      (node (ref "C19") (pin "2") (pinfunction "2_2") (pintype "passive"))
      (node (ref "R4") (pin "2") (pinfunction "2_2") (pintype "passive"))
    )
    (net (code "86") (name "Net-(D2-A)") (class "Default")
      (node (ref "D2") (pin "2") (pinfunction "A_2") (pintype "passive"))
      (node (ref "J5") (pin "1") (pinfunction "1_1") (pintype "passive"))
    )
    (net (code "87") (name "Net-(D4-A)") (class "Default")
      (node (ref "D4") (pin "2") (pinfunction "A_2") (pintype "passive"))
      (node (ref "J20") (pin "14") (pinfunction "14_14") (pintype "passive"))
    )
    (net (code "88") (name "Net-(D4-C)") (class "Default")
      (node (ref "D4") (pin "1") (pinfunction "C_1") (pintype "passive"))
      (node (ref "J20") (pin "11") (pinfunction "11_11") (pintype "passive"))
      (node (ref "J20") (pin "2") (pinfunction "2_2") (pintype "passive"))
      (node (ref "J20") (pin "5") (pinfunction "5_5") (pintype "passive"))
      (node (ref "J20") (pin "8") (pinfunction "8_8") (pintype "passive"))
    )
    (net (code "89") (name "Net-(D6-A)") (class "Default")
      (node (ref "D6") (pin "2") (pinfunction "A_2") (pintype "passive"))
      (node (ref "J6") (pin "14") (pinfunction "14_14") (pintype "passive"))
    )
    (net (code "90") (name "Net-(D6-C)") (class "Default")
      (node (ref "D6") (pin "1") (pinfunction "C_1") (pintype "passive"))
      (node (ref "J6") (pin "11") (pinfunction "11_11") (pintype "passive"))
      (node (ref "J6") (pin "2") (pinfunction "2_2") (pintype "passive"))
      (node (ref "J6") (pin "5") (pinfunction "5_5") (pintype "passive"))
      (node (ref "J6") (pin "8") (pinfunction "8_8") (pintype "passive"))
    )
    (net (code "91") (name "Net-(LED1-PadC)") (class "Default")
      (node (ref "LED1") (pin "C") (pinfunction "C_C") (pintype "passive"))
      (node (ref "R19") (pin "1") (pinfunction "1_1") (pintype "passive"))
    )
    (net (code "92") (name "Net-(U2-FB)") (class "Default")
      (node (ref "R22") (pin "1") (pinfunction "1_1") (pintype "passive"))
      (node (ref "R23") (pin "2") (pinfunction "2_2") (pintype "passive"))
      (node (ref "U2") (pin "4") (pinfunction "FB_4") (pintype "bidirectional"))
    )
    (net (code "93") (name "Net-(U2-OUT)") (class "Default")
      (node (ref "D1") (pin "C") (pinfunction "C_C") (pintype "passive"))
      (node (ref "L1") (pin "1") (pinfunction "1_1") (pintype "passive"))
      (node (ref "U2") (pin "2") (pinfunction "OUT_2") (pintype "bidirectional"))
    )
    (net (code "94") (name "Net-(U3-OUT1)") (class "Default")
      (node (ref "J2") (pin "3") (pinfunction "3_3") (pintype "passive"))
      (node (ref "U3") (pin "7") (pinfunction "OUT1_7") (pintype "output"))
    )
    (net (code "95") (name "Net-(U3-OUT2)") (class "Default")
      (node (ref "J2") (pin "4") (pinfunction "4_4") (pintype "passive"))
      (node (ref "U3") (pin "9") (pinfunction "OUT2_9") (pintype "input"))
    )
    (net (code "96") (name "Net-(U4-OUT1)") (class "Default")
      (node (ref "J1") (pin "2") (pinfunction "2_2") (pintype "passive"))
      (node (ref "U4") (pin "7") (pinfunction "OUT1_7") (pintype "output"))
    )
    (net (code "97") (name "Net-(U4-OUT2)") (class "Default")
      (node (ref "J1") (pin "1") (pinfunction "1_1") (pintype "passive"))
      (node (ref "U4") (pin "9") (pinfunction "OUT2_9") (pintype "input"))
    )
    (net (code "98") (name "Net-(U5-OUT1)") (class "Default")
      (node (ref "J1") (pin "4") (pinfunction "4_4") (pintype "passive"))
      (node (ref "U5") (pin "7") (pinfunction "OUT1_7") (pintype "output"))
    )
    (net (code "99") (name "Net-(U5-OUT2)") (class "Default")
      (node (ref "J1") (pin "3") (pinfunction "3_3") (pintype "passive"))
      (node (ref "U5") (pin "9") (pinfunction "OUT2_9") (pintype "input"))
    )
    (net (code "100") (name "Net-(U9-EN)") (class "Default")
      (node (ref "C27") (pin "2") (pinfunction "2_2") (pintype "passive"))
      (node (ref "R32") (pin "1") (pinfunction "1_1") (pintype "passive"))
      (node (ref "U9") (pin "7") (pinfunction "VR2_7") (pintype "bidirectional"))
      (node (ref "U9") (pin "8") (pinfunction "EN_8") (pintype "input"))
    )
    (net (code "101") (name "Net-(U14-AVDD)") (class "Default")
      (node (ref "C9") (pin "1") (pinfunction "1_1") (pintype "passive"))
      (node (ref "R1") (pin "2") (pinfunction "2_2") (pintype "passive"))
      (node (ref "U14") (pin "19") (pinfunction "AVDD_19") (pintype "power_in"))
    )
    (net (code "102") (name "Net-(U14-VDDCORE{slash}VCAP)") (class "Default")
      (node (ref "C3") (pin "2") (pinfunction "2_2") (pintype "passive"))
      (node (ref "U14") (pin "10") (pinfunction "VDDCORE/VCAP_10") (pintype "power_in"))
    )
    (net (code "103") (name "Net-(U14-~{MCLR{slash}}RG5)") (class "Default")
      (node (ref "R3") (pin "1") (pinfunction "1_1") (pintype "passive"))
      (node (ref "U14") (pin "7") (pinfunction "~{MCLR/}RG5_7") (pintype "input"))
    )
    (net (code "104") (name "Net-(U15-OUT1)") (class "Default")
      (node (ref "J2") (pin "1") (pinfunction "1_1") (pintype "passive"))
      (node (ref "U15") (pin "7") (pinfunction "OUT1_7") (pintype "output"))
    )
    (net (code "105") (name "Net-(U15-OUT2)") (class "Default")
      (node (ref "J2") (pin "2") (pinfunction "2_2") (pintype "passive"))
      (node (ref "U15") (pin "9") (pinfunction "OUT2_9") (pintype "input"))
    )
    (net (code "106") (name "unconnected-(J12-Pad1)") (class "Default")
      (node (ref "J12") (pin "1") (pinfunction "1_1") (pintype "passive"))
    )
    (net (code "107") (name "unconnected-(J14-Pad1)") (class "Default")
      (node (ref "J14") (pin "1") (pinfunction "1_1") (pintype "passive"))
    )
    (net (code "108") (name "unconnected-(U$1-1-PadP$2)") (class "Default")
      (node (ref "U$1") (pin "P$2") (pinfunction "1_P$2") (pintype "bidirectional"))
    )
    (net (code "109") (name "unconnected-(U$2-1-PadP$2)") (class "Default")
      (node (ref "U$2") (pin "P$2") (pinfunction "1_P$2") (pintype "bidirectional"))
    )
    (net (code "110") (name "unconnected-(U$7-1-PadP$2)") (class "Default")
      (node (ref "U$7") (pin "P$2") (pinfunction "1_P$2") (pintype "bidirectional"))
    )
    (net (code "111") (name "unconnected-(U$8-1-PadP$2)") (class "Default")
      (node (ref "U$8") (pin "P$2") (pinfunction "1_P$2") (pintype "bidirectional"))
    )
    (net (code "112") (name "unconnected-(U3-FAULT-Pad1)") (class "Default")
      (node (ref "U3") (pin "1") (pinfunction "FAULT_1") (pintype "output"))
    )
    (net (code "113") (name "unconnected-(U4-FAULT-Pad1)") (class "Default")
      (node (ref "U4") (pin "1") (pinfunction "FAULT_1") (pintype "output"))
    )
    (net (code "114") (name "unconnected-(U5-FAULT-Pad1)") (class "Default")
      (node (ref "U5") (pin "1") (pinfunction "FAULT_1") (pintype "output"))
    )
    (net (code "115") (name "unconnected-(U14-RE0{slash}~{RD{slash}}P2D-Pad2)") (class "Default")
      (node (ref "U14") (pin "2") (pinfunction "RE0/~{RD/}P2D_2") (pintype "bidirectional"))
    )
    (net (code "116") (name "unconnected-(U14-RE1{slash}~{WR{slash}}P2C-Pad1)") (class "Default")
      (node (ref "U14") (pin "1") (pinfunction "RE1/~{WR/}P2C_1") (pintype "bidirectional"))
    )
    (net (code "117") (name "unconnected-(U14-RG0{slash}ECCP3{slash}P3A-Pad3)") (class "Default")
      (node (ref "U14") (pin "3") (pinfunction "RG0/ECCP3/P3A_3") (pintype "bidirectional"))
    )
    (net (code "118") (name "unconnected-(U15-FAULT-Pad1)") (class "Default")
      (node (ref "U15") (pin "1") (pinfunction "FAULT_1") (pintype "output"))
    )
  )
)
